# front.net
KiCad netlist of a schematic drawn in EAGLE
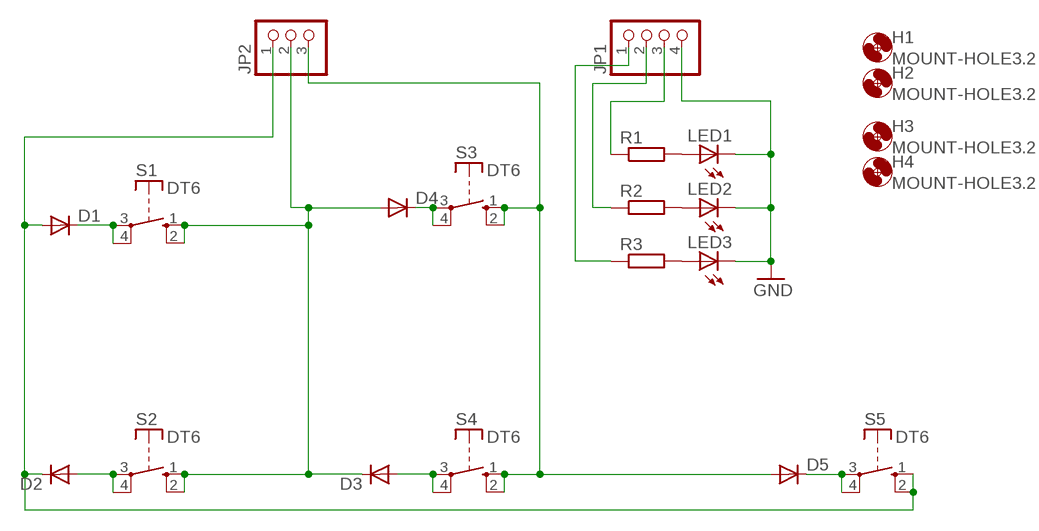
[diagram p0: schematic, sheet 1]

(export (version "E")
  (design (tool "Eeschema 10.0.6"))
  (components
    (comp (ref "D1")
      (value "DIODE-MINIMELF")
      (footprint "eagle-import:MINIMELF")
      (libsource (lib "eagle-import") (part "DIODE-MINIMELF"))
    )
    (comp (ref "D2")
      (value "DIODE-MINIMELF")
      (footprint "eagle-import:MINIMELF")
      (libsource (lib "eagle-import") (part "DIODE-MINIMELF"))
    )
    (comp (ref "D3")
      (value "DIODE-MINIMELF")
      (footprint "eagle-import:MINIMELF")
      (libsource (lib "eagle-import") (part "DIODE-MINIMELF"))
    )
    (comp (ref "D4")
      (value "DIODE-MINIMELF")
      (footprint "eagle-import:MINIMELF")
      (libsource (lib "eagle-import") (part "DIODE-MINIMELF"))
    )
    (comp (ref "D5")
      (value "DIODE-MINIMELF")
      (footprint "eagle-import:MINIMELF")
      (libsource (lib "eagle-import") (part "DIODE-MINIMELF"))
    )
    (comp (ref "H1")
      (value "MOUNT-HOLE3.2")
      (footprint "eagle-import:3,2")
      (libsource (lib "eagle-import") (part "MOUNT-HOLE3.2"))
    )
    (comp (ref "H2")
      (value "MOUNT-HOLE3.2")
      (footprint "eagle-import:3,2")
      (libsource (lib "eagle-import") (part "MOUNT-HOLE3.2"))
    )
    (comp (ref "H3")
      (value "MOUNT-HOLE3.2")
      (footprint "eagle-import:3,2")
      (libsource (lib "eagle-import") (part "MOUNT-HOLE3.2"))
    )
    (comp (ref "H4")
      (value "MOUNT-HOLE3.2")
      (footprint "eagle-import:3,2")
      (libsource (lib "eagle-import") (part "MOUNT-HOLE3.2"))
    )
    (comp (ref "JP1")
      (value "PINHD-1X4")
      (footprint "eagle-import:1X04")
      (libsource (lib "eagle-import") (part "PINHD-1X4"))
    )
    (comp (ref "JP2")
      (value "PINHD-1X3")
      (footprint "eagle-import:1X03")
      (libsource (lib "eagle-import") (part "PINHD-1X3"))
    )
    (comp (ref "LED1")
      (value "LED3MM")
      (footprint "eagle-import:LED3MM")
      (libsource (lib "eagle-import") (part "LED3MM"))
    )
    (comp (ref "LED2")
      (value "LED3MM")
      (footprint "eagle-import:LED3MM")
      (libsource (lib "eagle-import") (part "LED3MM"))
    )
    (comp (ref "LED3")
      (value "LED3MM")
      (footprint "eagle-import:LED3MM")
      (libsource (lib "eagle-import") (part "LED3MM"))
    )
    (comp (ref "R1")
      (value "R-EU_R0805")
      (footprint "eagle-import:R0805")
      (libsource (lib "eagle-import") (part "R-EU_R0805"))
    )
    (comp (ref "R2")
      (value "R-EU_R0805")
      (footprint "eagle-import:R0805")
      (libsource (lib "eagle-import") (part "R-EU_R0805"))
    )
    (comp (ref "R3")
      (value "R-EU_R0805")
      (footprint "eagle-import:R0805")
      (libsource (lib "eagle-import") (part "R-EU_R0805"))
    )
    (comp (ref "S1")
      (value "DT6")
      (footprint "eagle-import:DT6")
      (libsource (lib "eagle-import") (part "DT6"))
    )
    (comp (ref "S2")
      (value "DT6")
      (footprint "eagle-import:DT6")
      (libsource (lib "eagle-import") (part "DT6"))
    )
    (comp (ref "S3")
      (value "DT6")
      (footprint "eagle-import:DT6")
      (libsource (lib "eagle-import") (part "DT6"))
    )
    (comp (ref "S4")
      (value "DT6")
      (footprint "eagle-import:DT6")
      (libsource (lib "eagle-import") (part "DT6"))
    )
    (comp (ref "S5")
      (value "DT6")
      (footprint "eagle-import:DT6")
      (libsource (lib "eagle-import") (part "DT6"))
    )
  )
  (nets
    (net (code "1") (name "GND") (class "Default")
      (node (ref "JP1") (pin "4") (pinfunction "4_4") (pintype "passive"))
      (node (ref "LED1") (pin "K") (pinfunction "C_K") (pintype "passive"))
      (node (ref "LED2") (pin "K") (pinfunction "C_K") (pintype "passive"))
      (node (ref "LED3") (pin "K") (pinfunction "C_K") (pintype "passive"))
    )
    (net (code "2") (name "Net-(D1-PadA)") (class "Default")
      (node (ref "D1") (pin "A") (pinfunction "A_A") (pintype "passive"))
      (node (ref "D2") (pin "C") (pinfunction "C_C") (pintype "passive"))
      (node (ref "JP2") (pin "1") (pinfunction "1_1") (pintype "passive"))
      (node (ref "S5") (pin "1") (pinfunction "S_1") (pintype "passive"))
      (node (ref "S5") (pin "2") (pinfunction "S_2") (pintype "passive"))
    )
    (net (code "3") (name "Net-(D1-PadC)") (class "Default")
      (node (ref "D1") (pin "C") (pinfunction "C_C") (pintype "passive"))
      (node (ref "S1") (pin "3") (pinfunction "P_3") (pintype "passive"))
      (node (ref "S1") (pin "4") (pinfunction "P_4") (pintype "passive"))
    )
    (net (code "4") (name "Net-(D2-PadA)") (class "Default")
      (node (ref "D2") (pin "A") (pinfunction "A_A") (pintype "passive"))
      (node (ref "S2") (pin "3") (pinfunction "P_3") (pintype "passive"))
      (node (ref "S2") (pin "4") (pinfunction "P_4") (pintype "passive"))
    )
    (net (code "5") (name "Net-(D3-PadA)") (class "Default")
      (node (ref "D3") (pin "A") (pinfunction "A_A") (pintype "passive"))
      (node (ref "S4") (pin "3") (pinfunction "P_3") (pintype "passive"))
      (node (ref "S4") (pin "4") (pinfunction "P_4") (pintype "passive"))
    )
    (net (code "6") (name "Net-(D3-PadC)") (class "Default")
      (node (ref "D3") (pin "C") (pinfunction "C_C") (pintype "passive"))
      (node (ref "D4") (pin "A") (pinfunction "A_A") (pintype "passive"))
      (node (ref "JP2") (pin "2") (pinfunction "2_2") (pintype "passive"))
      (node (ref "S1") (pin "1") (pinfunction "S_1") (pintype "passive"))
      (node (ref "S1") (pin "2") (pinfunction "S_2") (pintype "passive"))
      (node (ref "S2") (pin "1") (pinfunction "S_1") (pintype "passive"))
      (node (ref "S2") (pin "2") (pinfunction "S_2") (pintype "passive"))
    )
    (net (code "7") (name "Net-(D4-PadC)") (class "Default")
      (node (ref "D4") (pin "C") (pinfunction "C_C") (pintype "passive"))
      (node (ref "S3") (pin "3") (pinfunction "P_3") (pintype "passive"))
      (node (ref "S3") (pin "4") (pinfunction "P_4") (pintype "passive"))
    )
    (net (code "8") (name "Net-(D5-PadA)") (class "Default")
      (node (ref "D5") (pin "A") (pinfunction "A_A") (pintype "passive"))
      (node (ref "JP2") (pin "3") (pinfunction "3_3") (pintype "passive"))
      (node (ref "S3") (pin "1") (pinfunction "S_1") (pintype "passive"))
      (node (ref "S3") (pin "2") (pinfunction "S_2") (pintype "passive"))
      (node (ref "S4") (pin "1") (pinfunction "S_1") (pintype "passive"))
      (node (ref "S4") (pin "2") (pinfunction "S_2") (pintype "passive"))
    )
    (net (code "9") (name "Net-(D5-PadC)") (class "Default")
      (node (ref "D5") (pin "C") (pinfunction "C_C") (pintype "passive"))
      (node (ref "S5") (pin "3") (pinfunction "P_3") (pintype "passive"))
      (node (ref "S5") (pin "4") (pinfunction "P_4") (pintype "passive"))
    )
    (net (code "10") (name "Net-(JP1-Pad1)") (class "Default")
      (node (ref "JP1") (pin "1") (pinfunction "1_1") (pintype "passive"))
      (node (ref "R3") (pin "1") (pinfunction "1_1") (pintype "passive"))
    )
    (net (code "11") (name "Net-(JP1-Pad2)") (class "Default")
      (node (ref "JP1") (pin "2") (pinfunction "2_2") (pintype "passive"))
      (node (ref "R2") (pin "1") (pinfunction "1_1") (pintype "passive"))
    )
    (net (code "12") (name "Net-(JP1-Pad3)") (class "Default")
      (node (ref "JP1") (pin "3") (pinfunction "3_3") (pintype "passive"))
      (node (ref "R1") (pin "1") (pinfunction "1_1") (pintype "passive"))
    )
    (net (code "13") (name "Net-(LED1-PadA)") (class "Default")
      (node (ref "LED1") (pin "A") (pinfunction "A_A") (pintype "passive"))
      (node (ref "R1") (pin "2") (pinfunction "2_2") (pintype "passive"))
    )
    (net (code "14") (name "Net-(LED2-PadA)") (class "Default")
      (node (ref "LED2") (pin "A") (pinfunction "A_A") (pintype "passive"))
      (node (ref "R2") (pin "2") (pinfunction "2_2") (pintype "passive"))
    )
    (net (code "15") (name "Net-(LED3-PadA)") (class "Default")
      (node (ref "LED3") (pin "A") (pinfunction "A_A") (pintype "passive"))
      (node (ref "R3") (pin "2") (pinfunction "2_2") (pintype "passive"))
    )
  )
)
